# power.net
KiCad netlist of a schematic drawn in Altium Designer
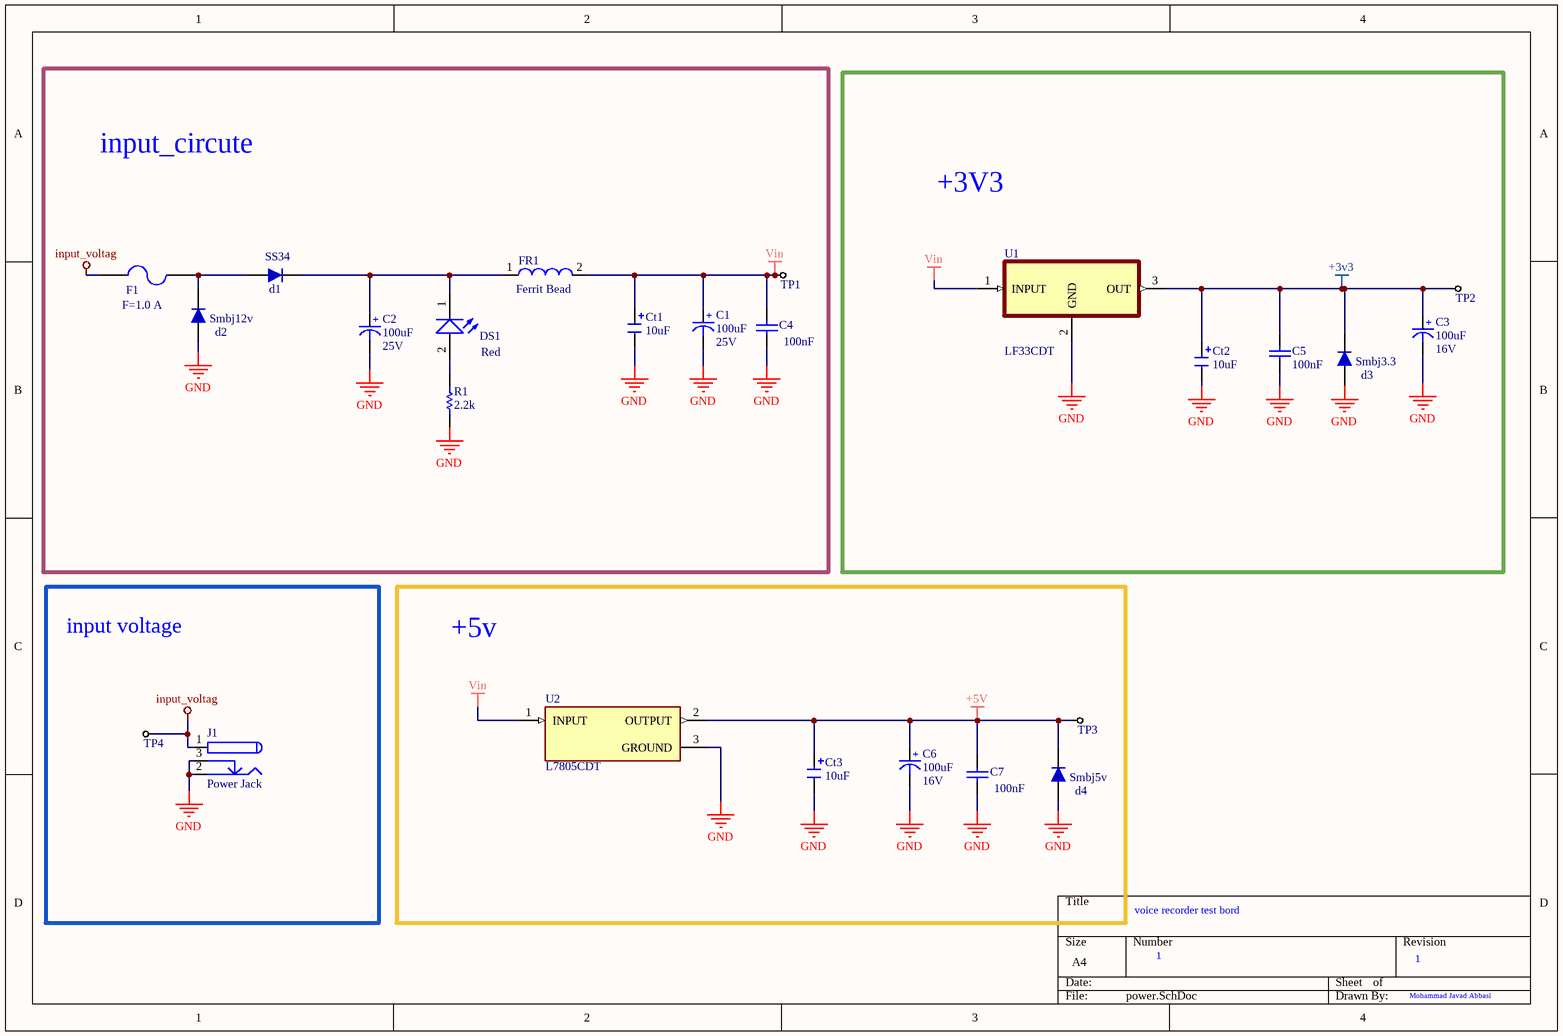
[diagram p0: power.SchDoc]

(export (version "E")
  (design (tool "Eeschema 10.0.6"))
  (components
    (comp (ref "C1")
      (value "100uF")
      (footprint "cap 03")
      (description "Polar Capacitor")
      (fields
        (field (name "VOLTAGE") "25V")
        (field (name "DESIGNER") "Eng. Saeid Jorablo")
        (field (name "PUBLISHER") "SJ Unlimited")
      )
      (libsource (lib "Schematic") (part "CAP_Polar"))
    )
    (comp (ref "C2")
      (value "100uF")
      (footprint "cap 03")
      (description "Polar Capacitor")
      (fields
        (field (name "VOLTAGE") "25V")
        (field (name "DESIGNER") "Eng. Saeid Jorablo")
        (field (name "PUBLISHER") "SJ Unlimited")
      )
      (libsource (lib "Schematic") (part "CAP_Polar"))
    )
    (comp (ref "C3")
      (value "100uF")
      (footprint "cap 03")
      (description "Polar Capacitor")
      (fields
        (field (name "VOLTAGE") "16V")
        (field (name "DESIGNER") "Eng. Saeid Jorablo")
        (field (name "PUBLISHER") "SJ Unlimited")
      )
      (libsource (lib "Schematic") (part "CAP_Polar"))
    )
    (comp (ref "C4")
      (value "100nF")
      (footprint "CAP805")
      (description "Capacitor")
      (fields (field (name "PUBLISHER") "Altium Limited"))
      (libsource (lib "componnect") (part "Cap"))
    )
    (comp (ref "C5")
      (value "100nF")
      (footprint "CAP805")
      (description "Capacitor")
      (fields (field (name "PUBLISHER") "Altium Limited"))
      (libsource (lib "componnect") (part "Cap"))
    )
    (comp (ref "C6")
      (value "100uF")
      (footprint "cap 03")
      (description "Polar Capacitor")
      (fields
        (field (name "VOLTAGE") "16V")
        (field (name "DESIGNER") "Eng. Saeid Jorablo")
        (field (name "PUBLISHER") "SJ Unlimited")
      )
      (libsource (lib "Schematic") (part "CAP_Polar"))
    )
    (comp (ref "C7")
      (value "100nF")
      (footprint "CAP805")
      (description "Capacitor")
      (fields (field (name "PUBLISHER") "Altium Limited"))
      (libsource (lib "componnect") (part "Cap"))
    )
    (comp (ref "Ct1")
      (value "10uF")
      (footprint "Tantalium Size B")
      (description "Tantalium Cap 10uF .... 100uF")
      (libsource (lib "componnect") (part "Capacitor Tantalium"))
    )
    (comp (ref "Ct2")
      (value "10uF")
      (footprint "Tantalium Size B")
      (description "Tantalium Cap 10uF .... 100uF")
      (libsource (lib "componnect") (part "Capacitor Tantalium"))
    )
    (comp (ref "Ct3")
      (value "10uF")
      (footprint "Tantalium Size B")
      (description "Tantalium Cap 10uF .... 100uF")
      (libsource (lib "componnect") (part "Capacitor Tantalium"))
    )
    (comp (ref "d1")
      (value "SS34")
      (footprint "DIODE SMA (DO-214AC)")
      (description "soutkey diod")
      (fields (field (name "MANUFACTURER") "DC COMPONENTS") (field (name "DESIGNER") "Abbas Basereh"))
      (libsource (lib "componnect") (part "1n4007 SMD M7"))
    )
    (comp (ref "d2")
      (value "Smbj12v")
      (footprint "DIODE SMA (DO-214AC)")
      (description "Smbj5.0")
      (fields (field (name "MANUFACTURER") "DC COMPONENTS") (field (name "DESIGNER") "Abbas Basereh"))
      (libsource (lib "componnect") (part "1n4007 SMD M7"))
    )
    (comp (ref "d3")
      (value "Smbj3.3")
      (footprint "DIODE SMA (DO-214AC)")
      (description "Smbj5.0")
      (fields (field (name "MANUFACTURER") "DC COMPONENTS") (field (name "DESIGNER") "Abbas Basereh"))
      (libsource (lib "componnect") (part "1n4007 SMD M7"))
    )
    (comp (ref "d4")
      (value "Smbj5v")
      (footprint "DIODE SMA (DO-214AC)")
      (description "Smbj5.0")
      (fields (field (name "MANUFACTURER") "DC COMPONENTS") (field (name "DESIGNER") "Abbas Basereh"))
      (libsource (lib "componnect") (part "1n4007 SMD M7"))
    )
    (comp (ref "DS1")
      (value "Red")
      (footprint "LED 1206")
      (description "SMD Mono-color Chip LED Waterclear")
      (fields (field (name "PART NUMBER") "150080BS75000") (field (name "PUBLISHER") "Ali Hafizi"))
      (libsource (lib "componnect") (part "LED SMD PACKAGE"))
    )
    (comp (ref "F1")
      (value "F=1.0 A")
      (footprint "1206 FUSE")
      (description "SMD Fuses 1206")
      (fields (field (name "DESIGNER") "Abbas Basereh"))
      (libsource (lib "componnect") (part "Fuse SMD1206"))
    )
    (comp (ref "FR1")
      (value "Ferrit Bead")
      (footprint "RES1206")
      (libsource (lib "Realy_Box_16_v5") (part "Ferrit Bead"))
    )
    (comp (ref "J1")
      (value "Power Jack")
      (footprint "Power Jack")
      (fields (field (name "DESIGNER") "Saeid Jorablo"))
      (libsource (lib "Schematic") (part "Power Jack"))
    )
    (comp (ref "R1")
      (value "2.2k")
      (footprint "RES0805")
      (description "RES 0805")
      (fields (field (name "DESIGNER") "Abbas Basereh"))
      (libsource (lib "componnect") (part "RES 0805 0.125W_1"))
    )
    (comp (ref "TP1")
      (value "~")
      (footprint "TP10")
      (description "Test Point")
      (fields (field (name "DESIGNER") "Eng. Saeid Jorablo"))
      (libsource (lib "General_06 Passive Components") (part "Test Point"))
    )
    (comp (ref "TP2")
      (value "~")
      (footprint "TP10")
      (description "Test Point")
      (fields (field (name "DESIGNER") "Eng. Saeid Jorablo"))
      (libsource (lib "General_06 Passive Components") (part "Test Point"))
    )
    (comp (ref "TP3")
      (value "~")
      (footprint "TP10")
      (description "Test Point")
      (fields (field (name "DESIGNER") "Eng. Saeid Jorablo"))
      (libsource (lib "General_06 Passive Components") (part "Test Point"))
    )
    (comp (ref "TP4")
      (value "~")
      (footprint "TP10")
      (description "Test Point")
      (fields (field (name "DESIGNER") "Eng. Saeid Jorablo"))
      (libsource (lib "General_06 Passive Components") (part "Test Point"))
    )
    (comp (ref "U1")
      (value "LF33CDT")
      (footprint "TO228P972X240-3N")
      (description "LDO, 0.45VDO, 1A, 3.3V, 1%, 3TO252")
      (fields (field (name "MF") "{'manufacturer': u'STMicroelectronics'}"))
      (libsource (lib "SnapEDA_Library") (part "LF33CDT"))
    )
    (comp (ref "U2")
      (value "L7805CDT")
      (footprint "VREG_L7805CDT")
      (fields (field (name "MF") "{'manufacturer': u'STMicroelectronics'}"))
      (libsource (lib "parking_eyes_Reciver") (part "L7805CDT"))
    )
  )
  (nets
    (net (code "1") (name "+3v3") (class "Default")
      (node (ref "C3") (pin "1") (pinfunction "+_1") (pintype "passive"))
      (node (ref "C5") (pin "2") (pinfunction "2_2") (pintype "passive"))
      (node (ref "Ct2") (pin "1") (pintype "passive"))
      (node (ref "TP2") (pin "1") (pinfunction "TP_1") (pintype "passive"))
      (node (ref "U1") (pin "3") (pinfunction "OUT_3") (pintype "output"))
      (node (ref "d3") (pin "2") (pintype "passive"))
    )
    (net (code "2") (name "+5V") (class "Default")
      (node (ref "C6") (pin "1") (pinfunction "+_1") (pintype "passive"))
      (node (ref "C7") (pin "2") (pinfunction "2_2") (pintype "passive"))
      (node (ref "Ct3") (pin "1") (pintype "passive"))
      (node (ref "TP3") (pin "1") (pinfunction "TP_1") (pintype "passive"))
      (node (ref "U2") (pin "2") (pinfunction "OUTPUT_2") (pintype "output"))
      (node (ref "d4") (pin "2") (pintype "passive"))
    )
    (net (code "3") (name "GND") (class "Default")
      (node (ref "C1") (pin "2") (pinfunction "-_2") (pintype "passive"))
      (node (ref "C2") (pin "2") (pinfunction "-_2") (pintype "passive"))
      (node (ref "C3") (pin "2") (pinfunction "-_2") (pintype "passive"))
      (node (ref "C4") (pin "1") (pinfunction "1_1") (pintype "passive"))
      (node (ref "C5") (pin "1") (pinfunction "1_1") (pintype "passive"))
      (node (ref "C6") (pin "2") (pinfunction "-_2") (pintype "passive"))
      (node (ref "C7") (pin "1") (pinfunction "1_1") (pintype "passive"))
      (node (ref "Ct1") (pin "2") (pintype "passive"))
      (node (ref "Ct2") (pin "2") (pintype "passive"))
      (node (ref "Ct3") (pin "2") (pintype "passive"))
      (node (ref "J1") (pin "2") (pinfunction "2_2") (pintype "power_in"))
      (node (ref "J1") (pin "3") (pinfunction "3_3") (pintype "power_in"))
      (node (ref "R1") (pin "1") (pinfunction "1_1") (pintype "passive"))
      (node (ref "U1") (pin "2") (pinfunction "GND_2") (pintype "passive"))
      (node (ref "U2") (pin "3") (pinfunction "GROUND_3") (pintype "power_in"))
      (node (ref "d2") (pin "1") (pintype "passive"))
      (node (ref "d3") (pin "1") (pintype "passive"))
      (node (ref "d4") (pin "1") (pintype "passive"))
    )
    (net (code "4") (name "Net-(C2-+)") (class "Default")
      (node (ref "C2") (pin "1") (pinfunction "+_1") (pintype "passive"))
      (node (ref "DS1") (pin "1") (pinfunction "K_1") (pintype "passive"))
      (node (ref "FR1") (pin "1") (pinfunction "1_1") (pintype "passive"))
      (node (ref "d1") (pin "2") (pintype "passive"))
    )
    (net (code "5") (name "Net-(DS1-A)") (class "Default")
      (node (ref "DS1") (pin "2") (pinfunction "A_2") (pintype "passive"))
      (node (ref "R1") (pin "2") (pinfunction "2_2") (pintype "passive"))
    )
    (net (code "6") (name "Net-(F1-Pad2)") (class "Default")
      (node (ref "F1") (pin "2") (pinfunction "2_2") (pintype "passive"))
      (node (ref "d1") (pin "1") (pintype "passive"))
      (node (ref "d2") (pin "2") (pintype "passive"))
    )
    (net (code "7") (name "Vin") (class "Default")
      (node (ref "C1") (pin "1") (pinfunction "+_1") (pintype "passive"))
      (node (ref "C4") (pin "2") (pinfunction "2_2") (pintype "passive"))
      (node (ref "Ct1") (pin "1") (pintype "passive"))
      (node (ref "FR1") (pin "2") (pinfunction "2_2") (pintype "passive"))
      (node (ref "TP1") (pin "1") (pinfunction "TP_1") (pintype "passive"))
      (node (ref "U1") (pin "1") (pinfunction "INPUT_1") (pintype "input"))
      (node (ref "U2") (pin "1") (pinfunction "INPUT_1") (pintype "input"))
    )
    (net (code "8") (name "input_voltag") (class "Default")
      (node (ref "F1") (pin "1") (pinfunction "1_1") (pintype "passive"))
      (node (ref "J1") (pin "1") (pinfunction "1_1") (pintype "power_in"))
      (node (ref "TP4") (pin "1") (pinfunction "TP_1") (pintype "passive"))
    )
  )
)
